# DSRLTEMPController.net
KiCad netlist of a schematic drawn in EAGLE
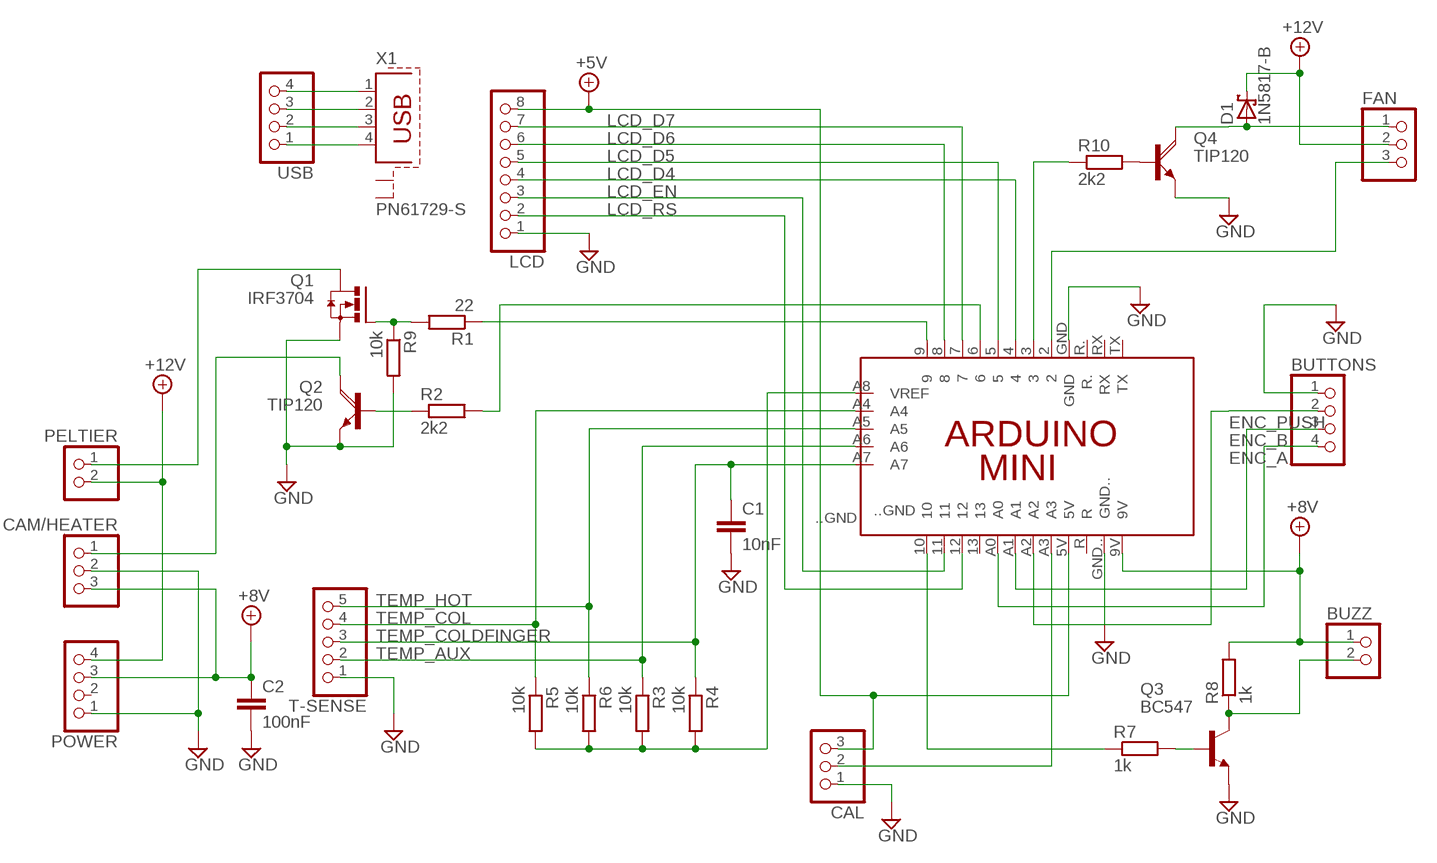
[diagram p0: schematic, sheet 1]

(export (version "E")
  (design (tool "Eeschema 10.0.6"))
  (components
    (comp (ref "BUTTONS")
      (value "PINHD-1X4")
      (footprint "eagle-import:1X04")
      (libsource (lib "eagle-import") (part "PINHD-1X4"))
    )
    (comp (ref "BUZZ")
      (value "PINHD-1X2")
      (footprint "eagle-import:1X02")
      (libsource (lib "eagle-import") (part "PINHD-1X2"))
    )
    (comp (ref "C1")
      (value "10nF")
      (footprint "eagle-import:C025-024X044")
      (libsource (lib "eagle-import") (part "C-EU025-024X044"))
    )
    (comp (ref "C2")
      (value "100nF")
      (footprint "eagle-import:C025_050-025X075")
      (libsource (lib "eagle-import") (part "C-EU025_050-025X075"))
    )
    (comp (ref "CAL")
      (value "PINHD-1X3")
      (footprint "eagle-import:1X03")
      (libsource (lib "eagle-import") (part "PINHD-1X3"))
    )
    (comp (ref "CAM/HEATER")
      (value "PINHD-1X3/90")
      (footprint "eagle-import:1X03_90")
      (libsource (lib "eagle-import") (part "PINHD-1X3/90"))
    )
    (comp (ref "D1")
      (value "1N5817-B")
      (footprint "eagle-import:DO41-7.6")
      (libsource (lib "eagle-import") (part "1N5817-B"))
    )
    (comp (ref "FAN")
      (value "PINHD-1X3/90")
      (footprint "eagle-import:1X03_90")
      (libsource (lib "eagle-import") (part "PINHD-1X3/90"))
    )
    (comp (ref "LCD")
      (value "PINHD-1X8")
      (footprint "eagle-import:1X08")
      (libsource (lib "eagle-import") (part "PINHD-1X8"))
    )
    (comp (ref "PCB1")
      (value "ARDUINO_MINI")
      (footprint "eagle-import:ARDUINO_MINI")
      (libsource (lib "eagle-import") (part "ARDUINO_MINI"))
    )
    (comp (ref "PELTIER")
      (value "PINHD-1X2/90")
      (footprint "eagle-import:1X02_90")
      (libsource (lib "eagle-import") (part "PINHD-1X2/90"))
    )
    (comp (ref "POWER")
      (value "PINHD-1X4/90")
      (footprint "eagle-import:1X04_90")
      (libsource (lib "eagle-import") (part "PINHD-1X4/90"))
    )
    (comp (ref "Q1")
      (value "IRF3704")
      (footprint "eagle-import:TO220AH")
      (libsource (lib "eagle-import") (part "IRF3704"))
    )
    (comp (ref "Q2")
      (value "TIP120")
      (footprint "eagle-import:TO220AH")
      (libsource (lib "eagle-import") (part "TIP120"))
    )
    (comp (ref "Q3")
      (value "BC547")
      (footprint "eagle-import:TO92")
      (libsource (lib "eagle-import") (part "BC547"))
    )
    (comp (ref "Q4")
      (value "TIP120")
      (footprint "eagle-import:TO220AH")
      (libsource (lib "eagle-import") (part "TIP120"))
    )
    (comp (ref "R1")
      (value "22")
      (footprint "eagle-import:0207_7")
      (libsource (lib "eagle-import") (part "R-EU_0207/7"))
    )
    (comp (ref "R2")
      (value "2k2")
      (footprint "eagle-import:0207_7")
      (libsource (lib "eagle-import") (part "R-EU_0207/7"))
    )
    (comp (ref "R3")
      (value "10k")
      (footprint "eagle-import:0207_7")
      (libsource (lib "eagle-import") (part "R-EU_0207/7"))
    )
    (comp (ref "R4")
      (value "10k")
      (footprint "eagle-import:0207_7")
      (libsource (lib "eagle-import") (part "R-EU_0207/7"))
    )
    (comp (ref "R5")
      (value "10k")
      (footprint "eagle-import:0207_7")
      (libsource (lib "eagle-import") (part "R-EU_0207/7"))
    )
    (comp (ref "R6")
      (value "10k")
      (footprint "eagle-import:0207_7")
      (libsource (lib "eagle-import") (part "R-EU_0207/7"))
    )
    (comp (ref "R7")
      (value "1k")
      (footprint "eagle-import:0207_7")
      (libsource (lib "eagle-import") (part "R-EU_0207/7"))
    )
    (comp (ref "R8")
      (value "1k")
      (footprint "eagle-import:0207_7")
      (libsource (lib "eagle-import") (part "R-EU_0207/7"))
    )
    (comp (ref "R9")
      (value "10k")
      (footprint "eagle-import:0207_7")
      (libsource (lib "eagle-import") (part "R-EU_0207/7"))
    )
    (comp (ref "R10")
      (value "2k2")
      (footprint "eagle-import:0207_7")
      (libsource (lib "eagle-import") (part "R-EU_0207/7"))
    )
    (comp (ref "T-SENSE")
      (value "PINHD-1X5")
      (footprint "eagle-import:1X05")
      (libsource (lib "eagle-import") (part "PINHD-1X5"))
    )
    (comp (ref "USB")
      (value "PINHD-1X4")
      (footprint "eagle-import:1X04")
      (libsource (lib "eagle-import") (part "PINHD-1X4"))
    )
    (comp (ref "X1")
      (value "PN61729-S")
      (footprint "eagle-import:PN61729-S")
      (libsource (lib "eagle-import") (part "PN61729-S"))
    )
  )
  (nets
    (net (code "1") (name "+5V") (class "Default")
      (node (ref "CAL") (pin "3") (pinfunction "3_3") (pintype "passive"))
      (node (ref "LCD") (pin "8") (pinfunction "8_8") (pintype "passive"))
      (node (ref "PCB1") (pin "5V") (pinfunction "5V_5V") (pintype "bidirectional"))
    )
    (net (code "2") (name "+8V") (class "Default")
      (node (ref "BUZZ") (pin "1") (pinfunction "1_1") (pintype "passive"))
      (node (ref "C2") (pin "1") (pinfunction "1_1") (pintype "passive"))
      (node (ref "CAM/HEATER") (pin "3") (pinfunction "3_3") (pintype "passive"))
      (node (ref "PCB1") (pin "9V") (pinfunction "9V_9V") (pintype "bidirectional"))
      (node (ref "POWER") (pin "3") (pinfunction "3_3") (pintype "passive"))
      (node (ref "R8") (pin "2") (pinfunction "2_2") (pintype "passive"))
    )
    (net (code "3") (name "+12V") (class "Default")
      (node (ref "D1") (pin "C") (pinfunction "C_C") (pintype "passive"))
      (node (ref "FAN") (pin "2") (pinfunction "2_2") (pintype "passive"))
      (node (ref "PELTIER") (pin "2") (pinfunction "2_2") (pintype "passive"))
      (node (ref "POWER") (pin "4") (pinfunction "4_4") (pintype "passive"))
    )
    (net (code "4") (name "/ENC_A") (class "Default")
      (node (ref "BUTTONS") (pin "4") (pinfunction "4_4") (pintype "passive"))
      (node (ref "PCB1") (pin "A0") (pinfunction "A0_A0") (pintype "bidirectional"))
    )
    (net (code "5") (name "/ENC_B") (class "Default")
      (node (ref "BUTTONS") (pin "3") (pinfunction "3_3") (pintype "passive"))
      (node (ref "PCB1") (pin "A1") (pinfunction "A1_A1") (pintype "bidirectional"))
    )
    (net (code "6") (name "/ENC_PUSH") (class "Default")
      (node (ref "BUTTONS") (pin "2") (pinfunction "2_2") (pintype "passive"))
      (node (ref "PCB1") (pin "A2") (pinfunction "A2_A2") (pintype "bidirectional"))
    )
    (net (code "7") (name "/LCD_D4") (class "Default")
      (node (ref "LCD") (pin "5") (pinfunction "5_5") (pintype "passive"))
      (node (ref "PCB1") (pin "5") (pinfunction "5_5") (pintype "bidirectional"))
    )
    (net (code "8") (name "/LCD_D5") (class "Default")
      (node (ref "LCD") (pin "4") (pinfunction "4_4") (pintype "passive"))
      (node (ref "PCB1") (pin "4") (pinfunction "4_4") (pintype "bidirectional"))
    )
    (net (code "9") (name "/LCD_D6") (class "Default")
      (node (ref "PCB1") (pin "3") (pinfunction "3_3") (pintype "bidirectional"))
      (node (ref "R10") (pin "1") (pinfunction "1_1") (pintype "passive"))
    )
    (net (code "10") (name "/LCD_D7") (class "Default")
      (node (ref "FAN") (pin "3") (pinfunction "3_3") (pintype "passive"))
      (node (ref "PCB1") (pin "2") (pinfunction "2_2") (pintype "bidirectional"))
    )
    (net (code "11") (name "/LCD_EN") (class "Default")
      (node (ref "LCD") (pin "3") (pinfunction "3_3") (pintype "passive"))
      (node (ref "PCB1") (pin "11") (pinfunction "11_11") (pintype "bidirectional"))
    )
    (net (code "12") (name "/LCD_RS") (class "Default")
      (node (ref "LCD") (pin "2") (pinfunction "2_2") (pintype "passive"))
      (node (ref "PCB1") (pin "12") (pinfunction "12_12") (pintype "bidirectional"))
    )
    (net (code "13") (name "/TEMP_AUX") (class "Default")
      (node (ref "PCB1") (pin "A6") (pinfunction "A6_A6") (pintype "bidirectional"))
      (node (ref "R3") (pin "1") (pinfunction "1_1") (pintype "passive"))
      (node (ref "T-SENSE") (pin "2") (pinfunction "2_2") (pintype "passive"))
    )
    (net (code "14") (name "/TEMP_COL") (class "Default")
      (node (ref "PCB1") (pin "A4") (pinfunction "A4_A4") (pintype "bidirectional"))
      (node (ref "R5") (pin "1") (pinfunction "1_1") (pintype "passive"))
      (node (ref "T-SENSE") (pin "4") (pinfunction "4_4") (pintype "passive"))
    )
    (net (code "15") (name "/TEMP_COLDFINGER") (class "Default")
      (node (ref "C1") (pin "1") (pinfunction "1_1") (pintype "passive"))
      (node (ref "PCB1") (pin "A7") (pinfunction "A7_A7") (pintype "bidirectional"))
      (node (ref "R4") (pin "1") (pinfunction "1_1") (pintype "passive"))
      (node (ref "T-SENSE") (pin "3") (pinfunction "3_3") (pintype "passive"))
    )
    (net (code "16") (name "/TEMP_HOT") (class "Default")
      (node (ref "PCB1") (pin "A5") (pinfunction "A5_A5") (pintype "bidirectional"))
      (node (ref "R6") (pin "1") (pinfunction "1_1") (pintype "passive"))
      (node (ref "T-SENSE") (pin "5") (pinfunction "5_5") (pintype "passive"))
    )
    (net (code "17") (name "GND") (class "Default")
      (node (ref "BUTTONS") (pin "1") (pinfunction "1_1") (pintype "passive"))
      (node (ref "C1") (pin "2") (pinfunction "2_2") (pintype "passive"))
      (node (ref "C2") (pin "2") (pinfunction "2_2") (pintype "passive"))
      (node (ref "CAL") (pin "1") (pinfunction "1_1") (pintype "passive"))
      (node (ref "CAM/HEATER") (pin "2") (pinfunction "2_2") (pintype "passive"))
      (node (ref "LCD") (pin "1") (pinfunction "1_1") (pintype "passive"))
      (node (ref "PCB1") (pin "GND") (pinfunction "GND_GND") (pintype "bidirectional"))
      (node (ref "PCB1") (pin "GND..") (pinfunction "GND.._GND..") (pintype "bidirectional"))
      (node (ref "POWER") (pin "1") (pinfunction "1_1") (pintype "passive"))
      (node (ref "Q1") (pin "E") (pinfunction "S_E") (pintype "passive"))
      (node (ref "Q2") (pin "E") (pinfunction "E_E") (pintype "passive"))
      (node (ref "Q3") (pin "1") (pinfunction "E_1") (pintype "passive"))
      (node (ref "Q4") (pin "E") (pinfunction "E_E") (pintype "passive"))
      (node (ref "R9") (pin "2") (pinfunction "2_2") (pintype "passive"))
      (node (ref "T-SENSE") (pin "1") (pinfunction "1_1") (pintype "passive"))
    )
    (net (code "18") (name "Net-(CAL-Pad2)") (class "Default")
      (node (ref "CAL") (pin "2") (pinfunction "2_2") (pintype "passive"))
      (node (ref "PCB1") (pin "A3") (pinfunction "A3_A3") (pintype "bidirectional"))
    )
    (net (code "19") (name "Net-(CAM/HEATER-Pad1)") (class "Default")
      (node (ref "CAM/HEATER") (pin "1") (pinfunction "1_1") (pintype "passive"))
      (node (ref "Q2") (pin "C") (pinfunction "C_C") (pintype "passive"))
    )
    (net (code "20") (name "Net-(D1-PadA)") (class "Default")
      (node (ref "D1") (pin "A") (pinfunction "A_A") (pintype "passive"))
      (node (ref "FAN") (pin "1") (pinfunction "1_1") (pintype "passive"))
      (node (ref "Q4") (pin "C") (pinfunction "C_C") (pintype "passive"))
    )
    (net (code "21") (name "Net-(LCD-Pad6)") (class "Default")
      (node (ref "LCD") (pin "6") (pinfunction "6_6") (pintype "passive"))
      (node (ref "PCB1") (pin "8") (pinfunction "8_8") (pintype "bidirectional"))
    )
    (net (code "22") (name "Net-(LCD-Pad7)") (class "Default")
      (node (ref "LCD") (pin "7") (pinfunction "7_7") (pintype "passive"))
      (node (ref "PCB1") (pin "7") (pinfunction "7_7") (pintype "bidirectional"))
    )
    (net (code "23") (name "Net-(PCB1-Pad6)") (class "Default")
      (node (ref "PCB1") (pin "6") (pinfunction "6_6") (pintype "bidirectional"))
      (node (ref "R2") (pin "2") (pinfunction "2_2") (pintype "passive"))
    )
    (net (code "24") (name "Net-(PCB1-Pad9)") (class "Default")
      (node (ref "PCB1") (pin "9") (pinfunction "9_9") (pintype "bidirectional"))
      (node (ref "R1") (pin "1") (pinfunction "1_1") (pintype "passive"))
    )
    (net (code "25") (name "Net-(PCB1-Pad10)") (class "Default")
      (node (ref "PCB1") (pin "10") (pinfunction "10_10") (pintype "bidirectional"))
      (node (ref "R7") (pin "1") (pinfunction "1_1") (pintype "passive"))
    )
    (net (code "26") (name "Net-(PCB1-VREF)") (class "Default")
      (node (ref "PCB1") (pin "A8") (pinfunction "VREF_A8") (pintype "bidirectional"))
      (node (ref "R3") (pin "2") (pinfunction "2_2") (pintype "passive"))
      (node (ref "R4") (pin "2") (pinfunction "2_2") (pintype "passive"))
      (node (ref "R5") (pin "2") (pinfunction "2_2") (pintype "passive"))
      (node (ref "R6") (pin "2") (pinfunction "2_2") (pintype "passive"))
    )
    (net (code "27") (name "Net-(Q1-D)") (class "Default")
      (node (ref "PELTIER") (pin "1") (pinfunction "1_1") (pintype "passive"))
      (node (ref "Q1") (pin "C") (pinfunction "D_C") (pintype "passive"))
    )
    (net (code "28") (name "Net-(Q1-G)") (class "Default")
      (node (ref "Q1") (pin "B") (pinfunction "G_B") (pintype "passive"))
      (node (ref "R1") (pin "2") (pinfunction "2_2") (pintype "passive"))
      (node (ref "R9") (pin "1") (pinfunction "1_1") (pintype "passive"))
    )
    (net (code "29") (name "Net-(Q2-PadB)") (class "Default")
      (node (ref "Q2") (pin "B") (pinfunction "B_B") (pintype "passive"))
      (node (ref "R2") (pin "1") (pinfunction "1_1") (pintype "passive"))
    )
    (net (code "30") (name "Net-(Q3-B)") (class "Default")
      (node (ref "Q3") (pin "2") (pinfunction "B_2") (pintype "passive"))
      (node (ref "R7") (pin "2") (pinfunction "2_2") (pintype "passive"))
    )
    (net (code "31") (name "Net-(Q3-C)") (class "Default")
      (node (ref "BUZZ") (pin "2") (pinfunction "2_2") (pintype "passive"))
      (node (ref "Q3") (pin "3") (pinfunction "C_3") (pintype "passive"))
      (node (ref "R8") (pin "1") (pinfunction "1_1") (pintype "passive"))
    )
    (net (code "32") (name "Net-(Q4-PadB)") (class "Default")
      (node (ref "Q4") (pin "B") (pinfunction "B_B") (pintype "passive"))
      (node (ref "R10") (pin "2") (pinfunction "2_2") (pintype "passive"))
    )
    (net (code "33") (name "Net-(USB-Pad1)") (class "Default")
      (node (ref "USB") (pin "1") (pinfunction "1_1") (pintype "passive"))
      (node (ref "X1") (pin "4") (pinfunction "4_4") (pintype "passive"))
    )
    (net (code "34") (name "Net-(USB-Pad2)") (class "Default")
      (node (ref "USB") (pin "2") (pinfunction "2_2") (pintype "passive"))
      (node (ref "X1") (pin "3") (pinfunction "3_3") (pintype "passive"))
    )
    (net (code "35") (name "Net-(USB-Pad3)") (class "Default")
      (node (ref "USB") (pin "3") (pinfunction "3_3") (pintype "passive"))
      (node (ref "X1") (pin "2") (pinfunction "2_2") (pintype "passive"))
    )
    (net (code "36") (name "Net-(USB-Pad4)") (class "Default")
      (node (ref "USB") (pin "4") (pinfunction "4_4") (pintype "passive"))
      (node (ref "X1") (pin "1") (pinfunction "1_1") (pintype "passive"))
    )
    (net (code "37") (name "unconnected-(PCB1-Pad..GND)") (class "Default")
      (node (ref "PCB1") (pin "..GND") (pinfunction "..GND_..GND") (pintype "bidirectional"))
    )
    (net (code "38") (name "unconnected-(PCB1-Pad13)") (class "Default")
      (node (ref "PCB1") (pin "13") (pinfunction "13_13") (pintype "bidirectional"))
    )
    (net (code "39") (name "unconnected-(PCB1-PadR)") (class "Default")
      (node (ref "PCB1") (pin "R") (pinfunction "R_R") (pintype "bidirectional"))
    )
    (net (code "40") (name "unconnected-(PCB1-PadR.)") (class "Default")
      (node (ref "PCB1") (pin "R.") (pinfunction "R._R.") (pintype "bidirectional"))
    )
    (net (code "41") (name "unconnected-(PCB1-PadRX)") (class "Default")
      (node (ref "PCB1") (pin "RX") (pinfunction "RX_RX") (pintype "bidirectional"))
    )
    (net (code "42") (name "unconnected-(PCB1-PadTX)") (class "Default")
      (node (ref "PCB1") (pin "TX") (pinfunction "TX_TX") (pintype "bidirectional"))
    )
    (net (code "43") (name "unconnected-(POWER-Pad2)") (class "Default")
      (node (ref "POWER") (pin "2") (pinfunction "2_2") (pintype "passive"))
    )
    (net (code "44") (name "unconnected-(X1-PadS1)") (class "Default")
      (node (ref "X1") (pin "S1") (pinfunction "S1_S1") (pintype "passive"))
    )
    (net (code "45") (name "unconnected-(X1-PadS2)") (class "Default")
      (node (ref "X1") (pin "S2") (pinfunction "S2_S2") (pintype "passive"))
    )
  )
)
